# 02_Connectors.net
KiCad netlist of a schematic drawn in Altium Designer
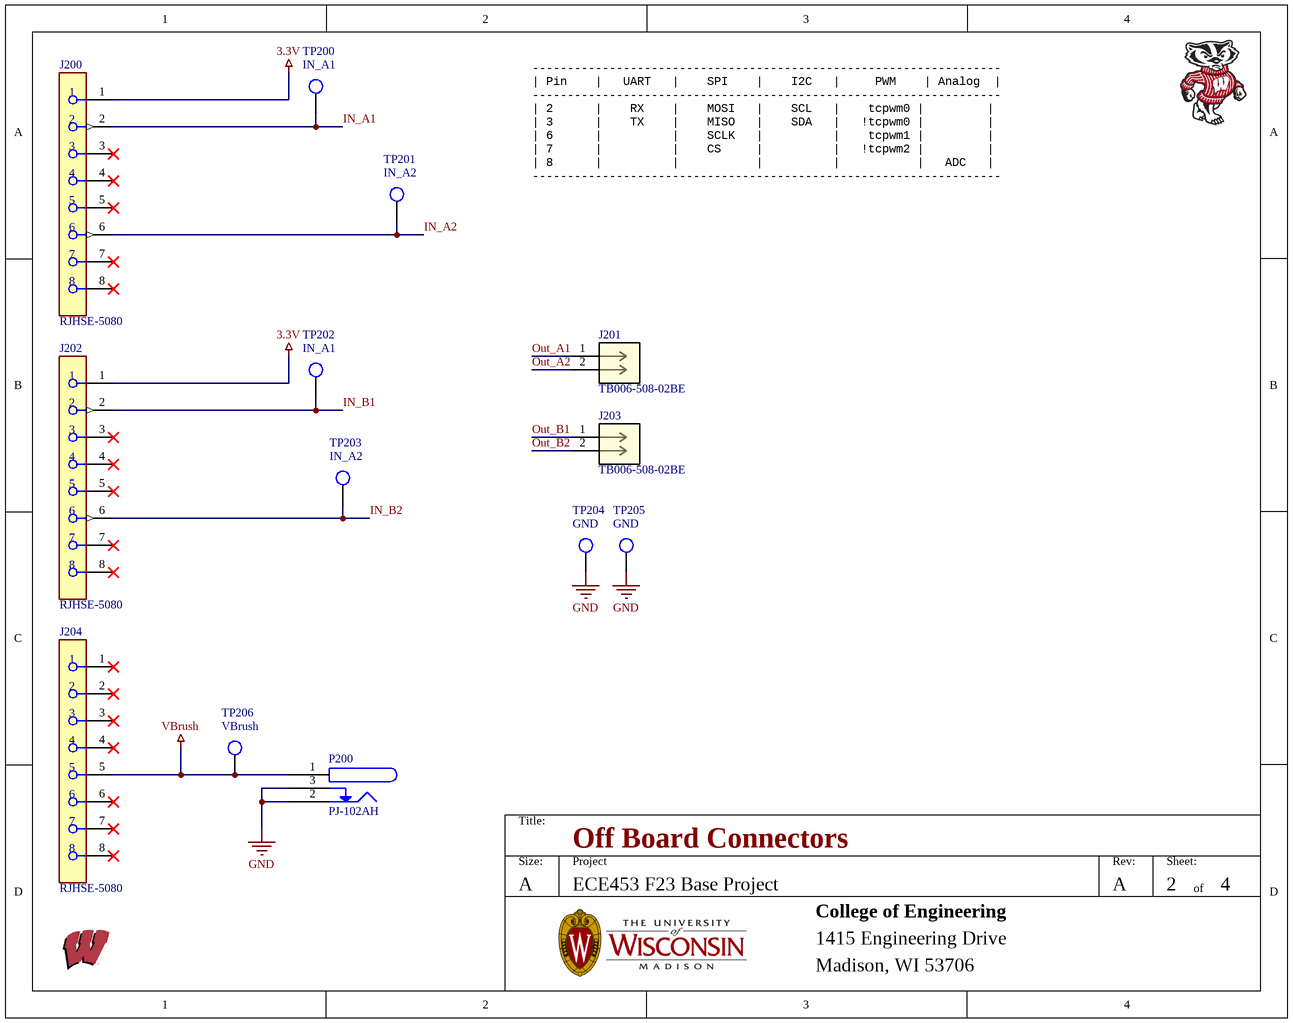
[diagram p0: 02_Connectors.SchDoc]

(export (version "E")
  (design (tool "Eeschema 10.0.6"))
  (components
    (comp (ref "J200")
      (value "RJHSE-5080")
      (footprint "FP-RJHSE-5080-MFG")
      (description "CONN MOD JACK 8P8C R/A UNSHLD")
      (fields
        (field (name "OCTOPART") "https://octopart.com/rjhse-5080-amphenol-45060")
        (field (name "MANUFACTURER") "Amphenol")
      )
      (libsource (lib "Altium Content Vault") (part "b0a0b555dd3abf3683e7c330df25cc4"))
    )
    (comp (ref "J201")
      (value "TB006-508-02BE")
      (footprint "CONN_TB006-508-02_CUD")
      (description "No Description Available")
      (fields (field (name "COPYRIGHT") "Copyright (C) 2023 Ultra Librarian. All rights reserved."))
      (libsource (lib "TB006-508-02BE") (part "TB006-508-02BE"))
    )
    (comp (ref "J202")
      (value "RJHSE-5080")
      (footprint "FP-RJHSE-5080-MFG")
      (description "CONN MOD JACK 8P8C R/A UNSHLD")
      (fields
        (field (name "OCTOPART") "https://octopart.com/rjhse-5080-amphenol-45060")
        (field (name "MANUFACTURER") "Amphenol")
      )
      (libsource (lib "Altium Content Vault") (part "b0a0b555dd3abf3683e7c330df25cc4"))
    )
    (comp (ref "J203")
      (value "TB006-508-02BE")
      (footprint "CONN_TB006-508-02_CUD")
      (description "No Description Available")
      (fields (field (name "COPYRIGHT") "Copyright (C) 2023 Ultra Librarian. All rights reserved."))
      (libsource (lib "TB006-508-02BE") (part "TB006-508-02BE"))
    )
    (comp (ref "J204")
      (value "RJHSE-5080")
      (footprint "FP-RJHSE-5080-MFG")
      (description "CONN MOD JACK 8P8C R/A UNSHLD")
      (fields
        (field (name "OCTOPART") "https://octopart.com/rjhse-5080-amphenol-45060")
        (field (name "MANUFACTURER") "Amphenol")
      )
      (libsource (lib "Altium Content Vault") (part "b0a0b555dd3abf3683e7c330df25cc4"))
    )
    (comp (ref "P200")
      (value "PJ-102")
      (footprint "PJ-102")
      (description "CONN PWR JACK 2.1X5.5MM HIGH CUR")
      (fields (field (name "MANUFACTURER") "CUI Inc") (field (name "MANUFACTURER PART NUMBER") "PJ-102AH"))
      (libsource (lib "ECE453") (part "CONN JACK PWR W/SW"))
    )
    (comp (ref "TP200")
      (value "IN_A1")
      (footprint "TP-SMC-1206")
      (description "Test Point SMD 1206")
      (fields
        (field (name "MANUFACTURER") "TE Connectivity (Tyco Electronics)")
        (field (name "MANUFACTURER PART NUMBER") "1625854-1")
      )
      (libsource (lib "ECE453") (part "TP_1206"))
    )
    (comp (ref "TP201")
      (value "IN_A2")
      (footprint "TP-SMC-1206")
      (description "Test Point SMD 1206")
      (fields
        (field (name "MANUFACTURER") "TE Connectivity (Tyco Electronics)")
        (field (name "MANUFACTURER PART NUMBER") "1625854-1")
      )
      (libsource (lib "ECE453") (part "TP_1206"))
    )
    (comp (ref "TP202")
      (value "IN_A1")
      (footprint "TP-SMC-1206")
      (description "Test Point SMD 1206")
      (fields
        (field (name "MANUFACTURER") "TE Connectivity (Tyco Electronics)")
        (field (name "MANUFACTURER PART NUMBER") "1625854-1")
      )
      (libsource (lib "ECE453") (part "TP_1206"))
    )
    (comp (ref "TP203")
      (value "IN_A2")
      (footprint "TP-SMC-1206")
      (description "Test Point SMD 1206")
      (fields
        (field (name "MANUFACTURER") "TE Connectivity (Tyco Electronics)")
        (field (name "MANUFACTURER PART NUMBER") "1625854-1")
      )
      (libsource (lib "ECE453") (part "TP_1206"))
    )
    (comp (ref "TP204")
      (value "GND")
      (footprint "TP-SMC-1206")
      (description "Test Point SMD 1206")
      (fields
        (field (name "MANUFACTURER") "TE Connectivity (Tyco Electronics)")
        (field (name "MANUFACTURER PART NUMBER") "1625854-1")
      )
      (libsource (lib "ECE453") (part "TP_1206"))
    )
    (comp (ref "TP205")
      (value "GND")
      (footprint "TP-SMC-1206")
      (description "Test Point SMD 1206")
      (fields
        (field (name "MANUFACTURER") "TE Connectivity (Tyco Electronics)")
        (field (name "MANUFACTURER PART NUMBER") "1625854-1")
      )
      (libsource (lib "ECE453") (part "TP_1206"))
    )
    (comp (ref "TP206")
      (value "VBrush")
      (footprint "TP-SMC-1206")
      (description "Test Point SMD 1206")
      (fields
        (field (name "MANUFACTURER") "TE Connectivity (Tyco Electronics)")
        (field (name "MANUFACTURER PART NUMBER") "1625854-1")
      )
      (libsource (lib "ECE453") (part "TP_1206"))
    )
  )
  (nets
    (net (code "1") (name "/IN_A1") (class "Default")
      (node (ref "J200") (pin "2") (pinfunction "2_2") (pintype "output"))
      (node (ref "TP200") (pin "1") (pintype "passive"))
    )
    (net (code "2") (name "/IN_A2") (class "Default")
      (node (ref "J200") (pin "6") (pinfunction "6_6") (pintype "output"))
      (node (ref "TP201") (pin "1") (pintype "passive"))
    )
    (net (code "3") (name "/IN_B1") (class "Default")
      (node (ref "J202") (pin "2") (pinfunction "2_2") (pintype "output"))
      (node (ref "TP202") (pin "1") (pintype "passive"))
    )
    (net (code "4") (name "/IN_B2") (class "Default")
      (node (ref "J202") (pin "6") (pinfunction "6_6") (pintype "output"))
      (node (ref "TP203") (pin "1") (pintype "passive"))
    )
    (net (code "5") (name "/Out_A1") (class "Default")
      (node (ref "J201") (pin "1") (pinfunction "1_1") (pintype "passive"))
    )
    (net (code "6") (name "/Out_A2") (class "Default")
      (node (ref "J201") (pin "2") (pinfunction "2_2") (pintype "passive"))
    )
    (net (code "7") (name "/Out_B1") (class "Default")
      (node (ref "J203") (pin "1") (pinfunction "1_1") (pintype "passive"))
    )
    (net (code "8") (name "/Out_B2") (class "Default")
      (node (ref "J203") (pin "2") (pinfunction "2_2") (pintype "passive"))
    )
    (net (code "9") (name "3.3V") (class "Default")
      (node (ref "J200") (pin "1") (pinfunction "1_1") (pintype "passive"))
      (node (ref "J202") (pin "1") (pinfunction "1_1") (pintype "passive"))
    )
    (net (code "10") (name "GND") (class "Default")
      (node (ref "P200") (pin "2") (pinfunction "2_2") (pintype "passive"))
      (node (ref "P200") (pin "3") (pinfunction "3_3") (pintype "passive"))
      (node (ref "TP204") (pin "1") (pintype "passive"))
      (node (ref "TP205") (pin "1") (pintype "passive"))
    )
    (net (code "11") (name "VBrush") (class "Default")
      (node (ref "J204") (pin "5") (pinfunction "5_5") (pintype "passive"))
      (node (ref "P200") (pin "1") (pinfunction "1_1") (pintype "passive"))
      (node (ref "TP206") (pin "1") (pintype "passive"))
    )
    (net (code "12") (name "unconnected-(J200-Pad3)") (class "Default")
      (node (ref "J200") (pin "3") (pinfunction "3_3") (pintype "passive+no_connect"))
    )
    (net (code "13") (name "unconnected-(J200-Pad4)") (class "Default")
      (node (ref "J200") (pin "4") (pinfunction "4_4") (pintype "passive+no_connect"))
    )
    (net (code "14") (name "unconnected-(J200-Pad5)") (class "Default")
      (node (ref "J200") (pin "5") (pinfunction "5_5") (pintype "passive+no_connect"))
    )
    (net (code "15") (name "unconnected-(J200-Pad7)") (class "Default")
      (node (ref "J200") (pin "7") (pinfunction "7_7") (pintype "passive+no_connect"))
    )
    (net (code "16") (name "unconnected-(J200-Pad8)") (class "Default")
      (node (ref "J200") (pin "8") (pinfunction "8_8") (pintype "passive+no_connect"))
    )
    (net (code "17") (name "unconnected-(J202-Pad3)") (class "Default")
      (node (ref "J202") (pin "3") (pinfunction "3_3") (pintype "passive+no_connect"))
    )
    (net (code "18") (name "unconnected-(J202-Pad4)") (class "Default")
      (node (ref "J202") (pin "4") (pinfunction "4_4") (pintype "passive+no_connect"))
    )
    (net (code "19") (name "unconnected-(J202-Pad5)") (class "Default")
      (node (ref "J202") (pin "5") (pinfunction "5_5") (pintype "passive+no_connect"))
    )
    (net (code "20") (name "unconnected-(J202-Pad7)") (class "Default")
      (node (ref "J202") (pin "7") (pinfunction "7_7") (pintype "passive+no_connect"))
    )
    (net (code "21") (name "unconnected-(J202-Pad8)") (class "Default")
      (node (ref "J202") (pin "8") (pinfunction "8_8") (pintype "passive+no_connect"))
    )
    (net (code "22") (name "unconnected-(J204-Pad1)") (class "Default")
      (node (ref "J204") (pin "1") (pinfunction "1_1") (pintype "passive+no_connect"))
    )
    (net (code "23") (name "unconnected-(J204-Pad2)") (class "Default")
      (node (ref "J204") (pin "2") (pinfunction "2_2") (pintype "output+no_connect"))
    )
    (net (code "24") (name "unconnected-(J204-Pad3)") (class "Default")
      (node (ref "J204") (pin "3") (pinfunction "3_3") (pintype "passive+no_connect"))
    )
    (net (code "25") (name "unconnected-(J204-Pad4)") (class "Default")
      (node (ref "J204") (pin "4") (pinfunction "4_4") (pintype "passive+no_connect"))
    )
    (net (code "26") (name "unconnected-(J204-Pad6)") (class "Default")
      (node (ref "J204") (pin "6") (pinfunction "6_6") (pintype "output+no_connect"))
    )
    (net (code "27") (name "unconnected-(J204-Pad7)") (class "Default")
      (node (ref "J204") (pin "7") (pinfunction "7_7") (pintype "passive+no_connect"))
    )
    (net (code "28") (name "unconnected-(J204-Pad8)") (class "Default")
      (node (ref "J204") (pin "8") (pinfunction "8_8") (pintype "passive+no_connect"))
    )
  )
)
